# DIG_PDU.net
KiCad netlist of a schematic drawn in Altium Designer
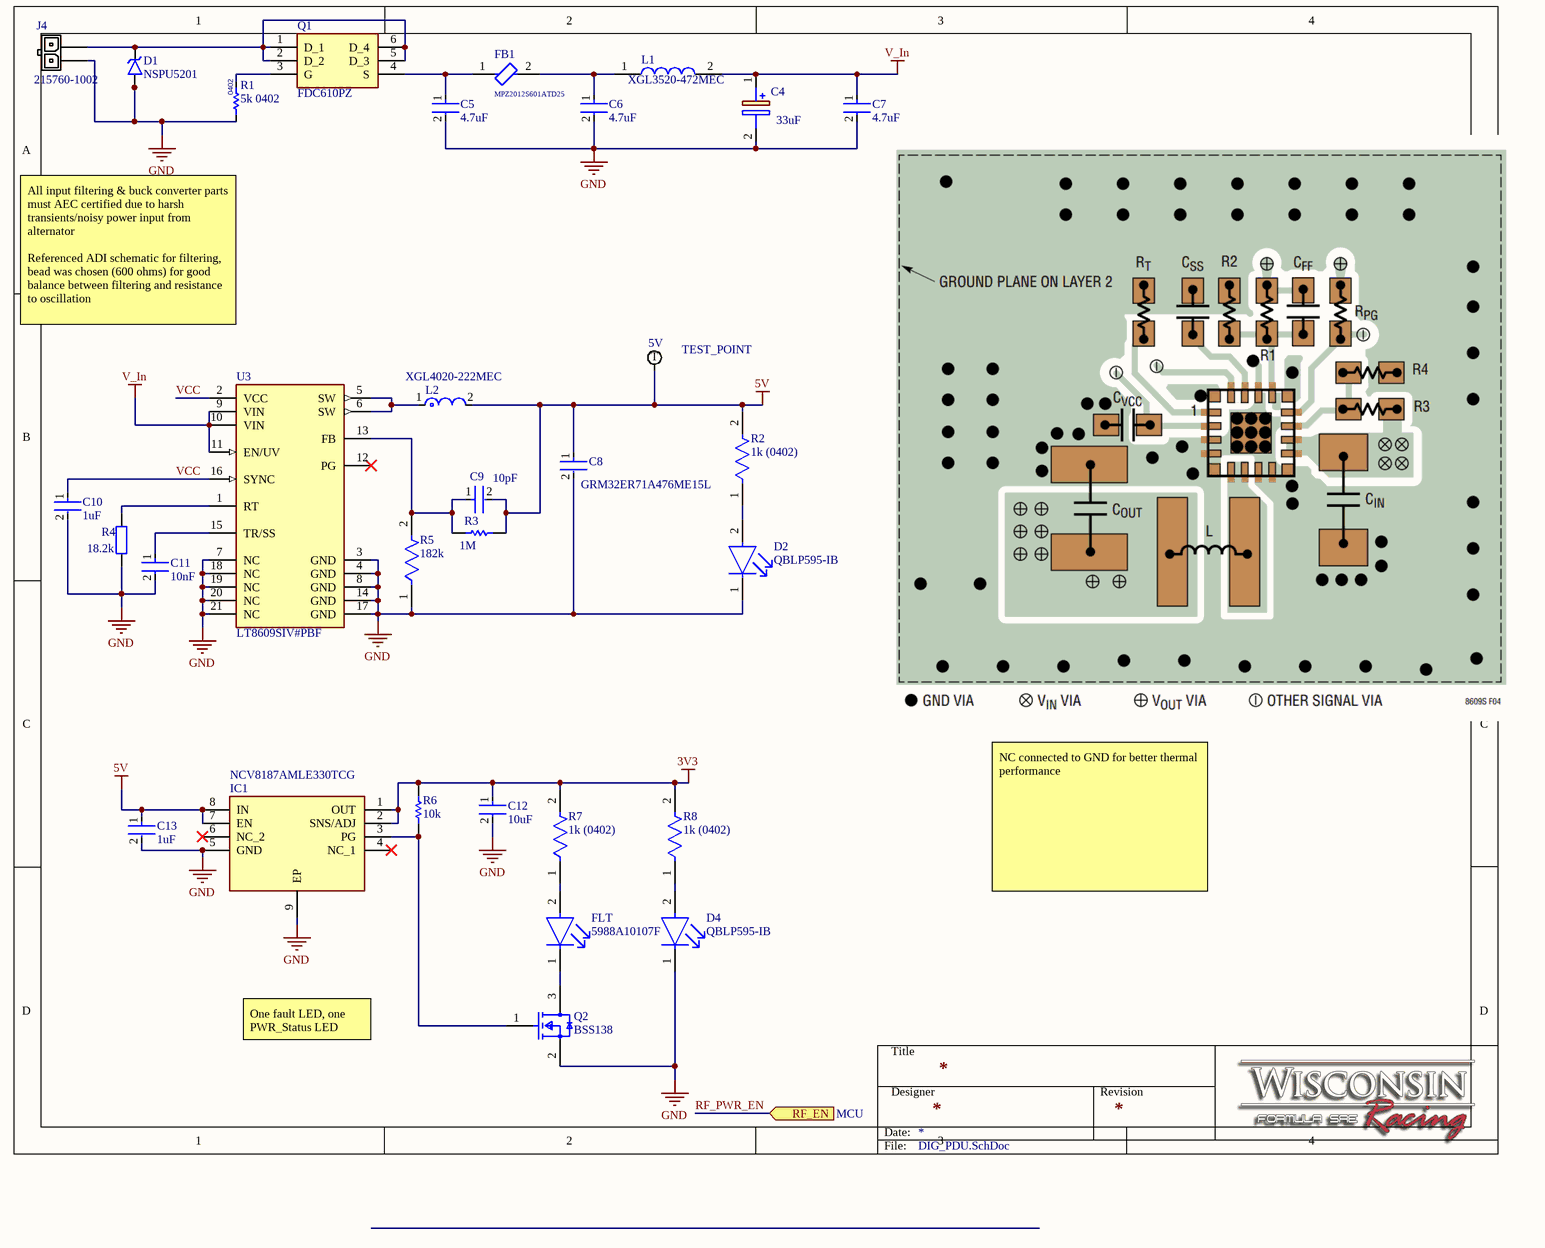
[diagram p0: DIG_PDU.SchDoc]

(export (version "E")
  (design (tool "Eeschema 10.0.6"))
  (components
    (comp (ref "5V")
      (value "TEST_POINT")
      (footprint "TEST_POINT-Footprint-1")
      (description "Pad for testing")
      (libsource (lib "University of Wisconsin Formula FSAE") (part "TEST_POINT"))
    )
    (comp (ref "C4")
      (value "HHXC500ARA330MF80G")
      (footprint "SamacSys:CAPAE660X800N")
      (description "Capacitor Polarised")
      (fields (field (name "MOUSER PART NUMBER") "661-HHXC500A330MF80G"))
      (libsource (lib "*") (part "HHXC500ARA330MF80G"))
    )
    (comp (ref "C5")
      (value "4.7uF")
      (footprint "FP-CGA4J-IPC_C")
      (description "Cap Ceramic 4.7uF 50V X7R 10% Pad SMD 0805 +125°C Automotive T/R")
      (libsource (lib "Altium Content Vault") (part "b4654b650e69147ec39a6b967a45e02"))
    )
    (comp (ref "C6")
      (value "4.7uF")
      (footprint "FP-CGA4J-IPC_C")
      (description "Cap Ceramic 4.7uF 50V X7R 10% Pad SMD 0805 +125°C Automotive T/R")
      (libsource (lib "Altium Content Vault") (part "b4654b650e69147ec39a6b967a45e02"))
    )
    (comp (ref "C7")
      (value "4.7uF")
      (footprint "FP-CGA4J-IPC_C")
      (description "Cap Ceramic 4.7uF 50V X7R 10% Pad SMD 0805 +125°C Automotive T/R")
      (libsource (lib "Altium Content Vault") (part "b4654b650e69147ec39a6b967a45e02"))
    )
    (comp (ref "C8")
      (value "GRM32ER71A476ME15L")
      (footprint "FP-GRM32E-0_3-0_2-IPC_A")
      (description "Chip Multilayer Ceramic Capacitors for General Purpose, 1210, 47uF, X7R, 15%, 20%, 10V")
      (fields (field (name "VOLTAGE") "10V") (field (name "TOLERANCE") "20%"))
      (libsource (lib "Altium Content Vault") (part "02cd4be3c70576c341d710602a673aa"))
    )
    (comp (ref "C9")
      (value "10pF")
      (footprint "FP-GCM155-0_05-IPC_C")
      (description "Ceramic Capacitor for Automotive 10pF ±5% 50VDC C0G 0402 Paper T/R")
      (fields (field (name "TOLERANCE") "5%"))
      (libsource (lib "Altium Content Vault") (part "02cd4be3c70576c341d710602a673aa"))
    )
    (comp (ref "C10")
      (value "1uF")
      (footprint "FP-GRT155-0_1-IPC_A")
      (description "Multi-Layer Ceramic Capacitor 1uF 25V X6S ±10% 0402 Paper T/R\r\n\r\nGRT155C81E105KE13D")
      (libsource (lib "Altium Content Vault") (part "02cd4be3c70576c341d710602a673aa"))
    )
    (comp (ref "C11")
      (value "10nF")
      (footprint "FP-GCM155-0_05-IPC_C")
      (description "Ceramic Capacitor for Automotive 10nF ±10% 50VDC X7R 0402 Paper T/R\r\n\r\nGCM155R71H103KA55D")
      (fields (field (name "TOLERANCE") "10%") (field (name "VOLTAGE") "50V"))
      (libsource (lib "Altium Content Vault") (part "02cd4be3c70576c341d710602a673aa"))
    )
    (comp (ref "C12")
      (value "10uF")
      (footprint "FP-GRM155-0_2-IPC_A")
      (description "Chip Multilayer Ceramic Capacitors for General Purpose, 0402, 10uF, X5R, 15%, 20%, 6.3V")
      (libsource (lib "Altium Content Vault") (part "b4654b650e69147ec39a6b967a45e02"))
    )
    (comp (ref "C13")
      (value "1uF")
      (footprint "FP-GRM155-0_1-IPC_C")
      (libsource (lib "Altium Content Vault") (part "11868f565c42a9108669ba33697ecf6"))
    )
    (comp (ref "D1")
      (value "NSPU5201")
      (footprint "NSPM5131MUTBG")
      (fields
        (field (name "ARROW PART NUMBER") "NSPU5201MUTBG")
        (field (name "MOUSER PART NUMBER") "863-NSPU5201MUTBG")
      )
      (libsource (lib "University of Wisconsin Formula FSAE") (part "NSPU5201MUTBG"))
    )
    (comp (ref "D2")
      (value "QBLP595-IB")
      (footprint "FP-QBLP595-IB-MFG")
      (description "LED BLUE CLEAR 0402 SMD")
      (libsource (lib "Altium Content Vault") (part "8706943c75ba83719d021d2fdc84c58"))
    )
    (comp (ref "D4")
      (value "QBLP595-IB")
      (footprint "FP-QBLP595-IB-MFG")
      (description "LED BLUE CLEAR 0402 SMD")
      (libsource (lib "Altium Content Vault") (part "8706943c75ba83719d021d2fdc84c58"))
    )
    (comp (ref "FB1")
      (value "MPZ2012S601ATD25")
      (footprint "BEADC2012X105N")
      (description "Ferrite Beads Multi-Layer Power 600Ohm 25% 100MHz 2A 100mOhm DCR 0805 Automotive T/R")
      (fields (field (name "MOUSER PART NUMBER") "810-MPZ2012S601ATD25"))
      (libsource (lib "University of Wisconsin Formula FSAE") (part "MPZ2012S601ATD25"))
    )
    (comp (ref "FLT")
      (value "5988A10107F")
      (footprint "FP-5988A10107F-MFG")
      (description "5988A10107F LED Uni-Color Red 2-Pin Chip 0402(1006Metric) T/R")
      (libsource (lib "Altium Content Vault") (part "8706943c75ba83719d021d2fdc84c58"))
    )
    (comp (ref "IC1")
      (value "NCV8187AMLE330TCG")
      (footprint "SamacSys:SON65P300X300X100-9N-D")
      (description "Integrated Circuit")
      (fields (field (name "MOUSER PART NUMBER") "863-CV8187AMLE330TCG"))
      (libsource (lib "*") (part "NCV8187AMLE330TCG"))
    )
    (comp (ref "J4")
      (value "215760-1002")
      (footprint "215760-1002-Footprint-1")
      (libsource (lib "University of Wisconsin Formula FSAE") (part "961102-6404-AR"))
    )
    (comp (ref "L1")
      (value "XGL3520-472MEC")
      (footprint "SamacSys:XGL3520472MEC")
      (description "Inductor")
      (libsource (lib "*") (part "XGL3520-472MEC"))
    )
    (comp (ref "L2")
      (value "XGL4020-222MEC")
      (footprint "FP-XGL4020-MFG")
      (description "Shielded Power Inductors")
      (libsource (lib "Altium Content Vault") (part "4cc4b267dca4c8e51f7102f422741d8"))
    )
    (comp (ref "Q1")
      (value "FDC610PZ")
      (footprint "SamacSys:SOT95P280X110-6N")
      (description "MOSFET (P-Channel)")
      (fields (field (name "MOUSER PART NUMBER") "512-FDC610PZ"))
      (libsource (lib "*") (part "FDC610PZ"))
    )
    (comp (ref "Q2")
      (value "BSS138")
      (footprint "FP-318-08-IPC_B")
      (description "MOSFET N-CH 50V 220MA SOT-23")
      (libsource (lib "Altium Content Vault") (part "3b9c635fedb024a5347a57b145af9cc"))
    )
    (comp (ref "R1")
      (value "5k 0402")
      (footprint "Res0402-Type-1")
      (fields (field (name "TOLERANCE") "1%") (field (name "POWER") "63mW"))
      (libsource (lib "University of Wisconsin Formula FSAE") (part "RES"))
    )
    (comp (ref "R2")
      (value "1k (0402)")
      (footprint "FP-RC0402-0_4-IPC_A")
      (description "RES 1K OHM 1% 1/16W 0402")
      (fields (field (name "TOLERANCE") "1%"))
      (libsource (lib "Altium Content Vault") (part "1029c3af85768c4190bb7ad29bc67b5"))
    )
    (comp (ref "R3")
      (value "1M")
      (footprint "RESC1005X40X25NL05T10")
      (fields (field (name "MANUFACTURER") "Yageo / Phycomp") (field (name "PART NUMBER") "RC0402FR-071ML"))
      (libsource (lib "Altium Content Vault") (part "RES"))
    )
    (comp (ref "R4")
      (value "18.2k")
      (footprint "WRIS-RSKS_0402")
      (description "Resistor, 18K2, 0.1W, Thick Film, 0402 Rohs Compliant: Yes")
      (libsource (lib "Altium Content Vault") (part "Resistor"))
    )
    (comp (ref "R5")
      (value "182k")
      (footprint "FP-AC0402-IPC_C")
      (description "RES 182kΩ ±1% 0.063W 0402")
      (fields (field (name "TOLERANCE") "1%"))
      (libsource (lib "Altium Content Vault") (part "1029c3af85768c4190bb7ad29bc67b5"))
    )
    (comp (ref "R6")
      (value "10k")
      (footprint "RESC1005X40X25ML05T05")
      (fields (field (name "PART NUMBER") "ERJ-2GEJ103X") (field (name "MANUFACTURER") "Panasonic"))
      (libsource (lib "Altium Content Vault") (part "RES"))
    )
    (comp (ref "R7")
      (value "1k (0402)")
      (footprint "FP-RC0402-0_4-IPC_A")
      (description "RES 1K OHM 1% 1/16W 0402")
      (fields (field (name "TOLERANCE") "1%"))
      (libsource (lib "Altium Content Vault") (part "1029c3af85768c4190bb7ad29bc67b5"))
    )
    (comp (ref "R8")
      (value "1k (0402)")
      (footprint "FP-RC0402-0_4-IPC_A")
      (description "RES 1K OHM 1% 1/16W 0402")
      (fields (field (name "TOLERANCE") "1%"))
      (libsource (lib "Altium Content Vault") (part "1029c3af85768c4190bb7ad29bc67b5"))
    )
    (comp (ref "U3")
      (value "LT8609SIV#PBF")
      (footprint "FP-LQFN-16-05-08-1516-MFG")
      (description "IC REG BUCK ADJUSTABLE 2A 16LQFN")
      (fields
        (field (name "OCTOPART") "https://octopart.com/lt8609siv%23pbf-analog+devices-88316701")
        (field (name "MANUFACTURER") "Analog Devices")
      )
      (libsource (lib "Altium Content Vault") (part "5cdaaed650003e075ab076d5d3b68d5"))
    )
  )
  (nets
    (net (code "2") (name "/VCC") (class "Default")
      (node (ref "C10") (pin "1") (pinfunction "1_1") (pintype "passive"))
      (node (ref "U3") (pin "16") (pinfunction "SYNC_16") (pintype "input"))
      (node (ref "U3") (pin "2") (pinfunction "VCC_2") (pintype "power_in"))
    )
    (net (code "3") (name "3V3") (class "Default")
      (node (ref "C12") (pin "1") (pinfunction "1_1") (pintype "passive"))
      (node (ref "IC1") (pin "1") (pinfunction "OUT_1") (pintype "passive"))
      (node (ref "IC1") (pin "2") (pinfunction "SNS/ADJ_2") (pintype "passive"))
      (node (ref "R6") (pin "2") (pinfunction "2_2") (pintype "passive"))
      (node (ref "R7") (pin "2") (pinfunction "2_2") (pintype "passive"))
      (node (ref "R8") (pin "2") (pinfunction "2_2") (pintype "passive"))
    )
    (net (code "4") (name "5V") (class "Default")
      (node (ref "5V") (pin "1") (pinfunction "1_1") (pintype "passive"))
      (node (ref "C13") (pin "1") (pinfunction "1_1") (pintype "passive"))
      (node (ref "C8") (pin "1") (pinfunction "1_1") (pintype "passive"))
      (node (ref "C9") (pin "2") (pinfunction "2_2") (pintype "passive"))
      (node (ref "IC1") (pin "7") (pinfunction "EN_7") (pintype "passive"))
      (node (ref "IC1") (pin "8") (pinfunction "IN_8") (pintype "passive"))
      (node (ref "L2") (pin "2") (pinfunction "2_2") (pintype "passive"))
      (node (ref "R2") (pin "2") (pinfunction "2_2") (pintype "passive"))
      (node (ref "R3") (pin "2") (pinfunction "2_2") (pintype "passive"))
    )
    (net (code "5") (name "GND") (class "Default")
      (node (ref "C10") (pin "2") (pinfunction "2_2") (pintype "passive"))
      (node (ref "C11") (pin "2") (pinfunction "2_2") (pintype "passive"))
      (node (ref "C12") (pin "2") (pinfunction "2_2") (pintype "passive"))
      (node (ref "C13") (pin "2") (pinfunction "2_2") (pintype "passive"))
      (node (ref "C4") (pin "2") (pinfunction "-_2") (pintype "passive"))
      (node (ref "C5") (pin "2") (pinfunction "2_2") (pintype "passive"))
      (node (ref "C6") (pin "2") (pinfunction "2_2") (pintype "passive"))
      (node (ref "C7") (pin "2") (pinfunction "2_2") (pintype "passive"))
      (node (ref "C8") (pin "2") (pinfunction "2_2") (pintype "passive"))
      (node (ref "D1") (pin "5") (pinfunction "GND_(A)_1_5") (pintype "passive"))
      (node (ref "D1") (pin "6") (pinfunction "GND_(A)_2_6") (pintype "passive"))
      (node (ref "D1") (pin "7") (pinfunction "GND_(A)_3_7") (pintype "passive"))
      (node (ref "D1") (pin "8") (pinfunction "GND_(A)_4_8") (pintype "passive"))
      (node (ref "D2") (pin "1") (pinfunction "C_1") (pintype "passive"))
      (node (ref "D4") (pin "1") (pinfunction "C_1") (pintype "passive"))
      (node (ref "IC1") (pin "5") (pinfunction "GND_5") (pintype "passive"))
      (node (ref "IC1") (pin "9") (pinfunction "EP_9") (pintype "passive"))
      (node (ref "J4") (pin "2") (pinfunction "2_2") (pintype "passive"))
      (node (ref "Q2") (pin "2") (pinfunction "S_2") (pintype "passive"))
      (node (ref "R1") (pin "1") (pinfunction "1_1") (pintype "passive"))
      (node (ref "R4") (pin "1") (pinfunction "1_1") (pintype "passive"))
      (node (ref "R5") (pin "1") (pinfunction "1_1") (pintype "passive"))
      (node (ref "U3") (pin "14") (pinfunction "GND_14") (pintype "power_in"))
      (node (ref "U3") (pin "17") (pinfunction "GND_17") (pintype "power_in"))
      (node (ref "U3") (pin "18") (pinfunction "NC_18") (pintype "passive"))
      (node (ref "U3") (pin "19") (pinfunction "NC_19") (pintype "passive"))
      (node (ref "U3") (pin "20") (pinfunction "NC_20") (pintype "passive"))
      (node (ref "U3") (pin "21") (pinfunction "NC_21") (pintype "passive"))
      (node (ref "U3") (pin "3") (pinfunction "GND_3") (pintype "power_in"))
      (node (ref "U3") (pin "4") (pinfunction "GND_4") (pintype "power_in"))
      (node (ref "U3") (pin "7") (pinfunction "NC_7") (pintype "passive"))
      (node (ref "U3") (pin "8") (pinfunction "GND_8") (pintype "power_in"))
    )
    (net (code "6") (name "Net-(C6-Pad1)") (class "Default")
      (node (ref "C6") (pin "1") (pinfunction "1_1") (pintype "passive"))
      (node (ref "FB1") (pin "2") (pinfunction "2_2") (pintype "passive"))
      (node (ref "L1") (pin "1") (pinfunction "1_1") (pintype "passive"))
    )
    (net (code "7") (name "Net-(D2-A)") (class "Default")
      (node (ref "D2") (pin "2") (pinfunction "A_2") (pintype "passive"))
      (node (ref "R2") (pin "1") (pinfunction "1_1") (pintype "passive"))
    )
    (net (code "8") (name "Net-(D4-A)") (class "Default")
      (node (ref "D4") (pin "2") (pinfunction "A_2") (pintype "passive"))
      (node (ref "R8") (pin "1") (pinfunction "1_1") (pintype "passive"))
    )
    (net (code "9") (name "Net-(FLT-A)") (class "Default")
      (node (ref "FLT") (pin "2") (pinfunction "A_2") (pintype "passive"))
      (node (ref "R7") (pin "1") (pinfunction "1_1") (pintype "passive"))
    )
    (net (code "10") (name "Net-(FLT-C)") (class "Default")
      (node (ref "FLT") (pin "1") (pinfunction "C_1") (pintype "passive"))
      (node (ref "Q2") (pin "3") (pinfunction "D_3") (pintype "passive"))
    )
    (net (code "11") (name "Net-(IC1-PG)") (class "Default")
      (node (ref "IC1") (pin "3") (pinfunction "PG_3") (pintype "passive"))
      (node (ref "Q2") (pin "1") (pinfunction "G_1") (pintype "passive"))
      (node (ref "R6") (pin "1") (pinfunction "1_1") (pintype "passive"))
    )
    (net (code "12") (name "Net-(L2-Pad1)") (class "Default")
      (node (ref "L2") (pin "1") (pinfunction "1_1") (pintype "passive"))
      (node (ref "U3") (pin "5") (pinfunction "SW_5") (pintype "output"))
      (node (ref "U3") (pin "6") (pinfunction "SW_6") (pintype "output"))
    )
    (net (code "13") (name "Net-(Q1-D_1)") (class "Default")
      (node (ref "D1") (pin "1") (pinfunction "1_1") (pintype "passive"))
      (node (ref "D1") (pin "2") (pinfunction "2_2") (pintype "passive"))
      (node (ref "J4") (pin "1") (pinfunction "1_1") (pintype "passive"))
      (node (ref "Q1") (pin "1") (pinfunction "D_1_1") (pintype "passive"))
      (node (ref "Q1") (pin "2") (pinfunction "D_2_2") (pintype "passive"))
      (node (ref "Q1") (pin "5") (pinfunction "D_3_5") (pintype "passive"))
      (node (ref "Q1") (pin "6") (pinfunction "D_4_6") (pintype "passive"))
    )
    (net (code "14") (name "Net-(Q1-G)") (class "Default")
      (node (ref "Q1") (pin "3") (pinfunction "G_3") (pintype "passive"))
      (node (ref "R1") (pin "2") (pinfunction "2_2") (pintype "passive"))
    )
    (net (code "15") (name "Net-(Q1-S)") (class "Default")
      (node (ref "C5") (pin "1") (pinfunction "1_1") (pintype "passive"))
      (node (ref "FB1") (pin "1") (pinfunction "1_1") (pintype "passive"))
      (node (ref "Q1") (pin "4") (pinfunction "S_4") (pintype "passive"))
    )
    (net (code "16") (name "Net-(U3-FB)") (class "Default")
      (node (ref "C9") (pin "1") (pinfunction "1_1") (pintype "passive"))
      (node (ref "R3") (pin "1") (pinfunction "1_1") (pintype "passive"))
      (node (ref "R5") (pin "2") (pinfunction "2_2") (pintype "passive"))
      (node (ref "U3") (pin "13") (pinfunction "FB_13") (pintype "passive"))
    )
    (net (code "17") (name "Net-(U3-RT)") (class "Default")
      (node (ref "R4") (pin "2") (pinfunction "2_2") (pintype "passive"))
      (node (ref "U3") (pin "1") (pinfunction "RT_1") (pintype "passive"))
    )
    (net (code "18") (name "Net-(U3-TR{slash}SS)") (class "Default")
      (node (ref "C11") (pin "1") (pinfunction "1_1") (pintype "passive"))
      (node (ref "U3") (pin "15") (pinfunction "TR/SS_15") (pintype "passive"))
    )
    (net (code "19") (name "V_In") (class "Default")
      (node (ref "C4") (pin "1") (pinfunction "+_1") (pintype "passive"))
      (node (ref "C7") (pin "1") (pinfunction "1_1") (pintype "passive"))
      (node (ref "L1") (pin "2") (pinfunction "2_2") (pintype "passive"))
      (node (ref "U3") (pin "10") (pinfunction "VIN_10") (pintype "power_in"))
      (node (ref "U3") (pin "11") (pinfunction "EN/UV_11") (pintype "input"))
      (node (ref "U3") (pin "9") (pinfunction "VIN_9") (pintype "power_in"))
    )
    (net (code "20") (name "unconnected-(IC1-NC_1-Pad4)") (class "Default")
      (node (ref "IC1") (pin "4") (pinfunction "NC_1_4") (pintype "passive+no_connect"))
    )
    (net (code "21") (name "unconnected-(IC1-NC_2-Pad6)") (class "Default")
      (node (ref "IC1") (pin "6") (pinfunction "NC_2_6") (pintype "passive+no_connect"))
    )
    (net (code "22") (name "unconnected-(U3-PG-Pad12)") (class "Default")
      (node (ref "U3") (pin "12") (pinfunction "PG_12") (pintype "open_collector+no_connect"))
    )
  )
)
